# DisplayBank.net
KiCad netlist of a schematic drawn in EAGLE
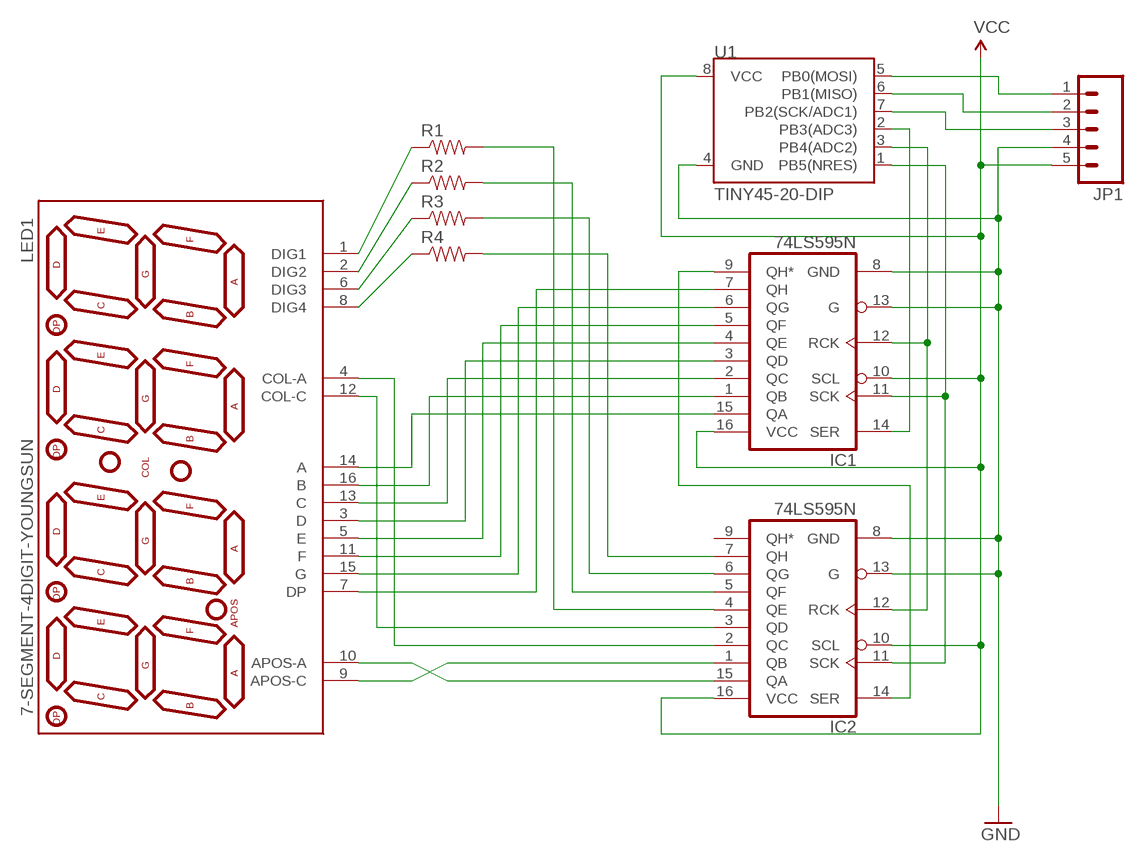
[diagram p0: schematic, sheet 1]

(export (version "E")
  (design (tool "Eeschema 10.0.6"))
  (components
    (comp (ref "IC1")
      (value "74LS595N")
      (footprint "eagle-import:DIL16")
      (libsource (lib "eagle-import") (part "74595NLS"))
    )
    (comp (ref "IC2")
      (value "74LS595N")
      (footprint "eagle-import:DIL16")
      (libsource (lib "eagle-import") (part "74595NLS"))
    )
    (comp (ref "JP1")
      (value "M05NO_SILK")
      (footprint "eagle-import:1X05_NO_SILK")
      (libsource (lib "eagle-import") (part "M05NO_SILK"))
    )
    (comp (ref "LED1")
      (value "7-SEGMENT-4DIGIT-YOUNGSUN")
      (footprint "eagle-import:7-SEGMENT-4DIGIT-YOUNGSUN")
      (libsource (lib "eagle-import") (part "7-SEGMENT-4DIGIT-YOUNGSUN"))
    )
    (comp (ref "R1")
      (value "RESISTORPTH-1/4W")
      (footprint "eagle-import:AXIAL-0.4")
      (libsource (lib "eagle-import") (part "RESISTORPTH-1/4W"))
    )
    (comp (ref "R2")
      (value "RESISTORPTH-1/4W")
      (footprint "eagle-import:AXIAL-0.4")
      (libsource (lib "eagle-import") (part "RESISTORPTH-1/4W"))
    )
    (comp (ref "R3")
      (value "RESISTORPTH-1/4W")
      (footprint "eagle-import:AXIAL-0.4")
      (libsource (lib "eagle-import") (part "RESISTORPTH-1/4W"))
    )
    (comp (ref "R4")
      (value "RESISTORPTH-1/4W")
      (footprint "eagle-import:AXIAL-0.4")
      (libsource (lib "eagle-import") (part "RESISTORPTH-1/4W"))
    )
    (comp (ref "U1")
      (value "TINY45-20-DIP")
      (footprint "eagle-import:DIP08")
      (libsource (lib "eagle-import") (part "ATTINY45TINY45-20-DIP"))
    )
  )
  (nets
    (net (code "1") (name "GND") (class "Default")
      (node (ref "IC1") (pin "13") (pinfunction "G_13") (pintype "input"))
      (node (ref "IC1") (pin "8") (pinfunction "GND_8") (pintype "power_in"))
      (node (ref "IC2") (pin "13") (pinfunction "G_13") (pintype "input"))
      (node (ref "IC2") (pin "8") (pinfunction "GND_8") (pintype "power_in"))
      (node (ref "JP1") (pin "4") (pinfunction "4_4") (pintype "passive"))
      (node (ref "U1") (pin "4") (pinfunction "GND_4") (pintype "bidirectional"))
    )
    (net (code "2") (name "Net-(IC1-QA)") (class "Default")
      (node (ref "IC1") (pin "15") (pinfunction "QA_15") (pintype "tri_state"))
      (node (ref "LED1") (pin "14") (pinfunction "A_14") (pintype "bidirectional"))
    )
    (net (code "3") (name "Net-(IC1-QB)") (class "Default")
      (node (ref "IC1") (pin "1") (pinfunction "QB_1") (pintype "tri_state"))
      (node (ref "LED1") (pin "16") (pinfunction "B_16") (pintype "bidirectional"))
    )
    (net (code "4") (name "Net-(IC1-QC)") (class "Default")
      (node (ref "IC1") (pin "2") (pinfunction "QC_2") (pintype "tri_state"))
      (node (ref "LED1") (pin "13") (pinfunction "C_13") (pintype "bidirectional"))
    )
    (net (code "5") (name "Net-(IC1-QD)") (class "Default")
      (node (ref "IC1") (pin "3") (pinfunction "QD_3") (pintype "tri_state"))
      (node (ref "LED1") (pin "3") (pinfunction "D_3") (pintype "bidirectional"))
    )
    (net (code "6") (name "Net-(IC1-QE)") (class "Default")
      (node (ref "IC1") (pin "4") (pinfunction "QE_4") (pintype "tri_state"))
      (node (ref "LED1") (pin "5") (pinfunction "E_5") (pintype "bidirectional"))
    )
    (net (code "7") (name "Net-(IC1-QF)") (class "Default")
      (node (ref "IC1") (pin "5") (pinfunction "QF_5") (pintype "tri_state"))
      (node (ref "LED1") (pin "11") (pinfunction "F_11") (pintype "bidirectional"))
    )
    (net (code "8") (name "Net-(IC1-QG)") (class "Default")
      (node (ref "IC1") (pin "6") (pinfunction "QG_6") (pintype "tri_state"))
      (node (ref "LED1") (pin "15") (pinfunction "G_15") (pintype "bidirectional"))
    )
    (net (code "9") (name "Net-(IC1-QH)") (class "Default")
      (node (ref "IC1") (pin "7") (pinfunction "QH_7") (pintype "tri_state"))
      (node (ref "LED1") (pin "7") (pinfunction "DP_7") (pintype "bidirectional"))
    )
    (net (code "10") (name "Net-(IC1-QH*)") (class "Default")
      (node (ref "IC1") (pin "9") (pinfunction "QH*_9") (pintype "tri_state"))
      (node (ref "IC2") (pin "14") (pinfunction "SER_14") (pintype "input"))
    )
    (net (code "11") (name "Net-(IC1-RCK)") (class "Default")
      (node (ref "IC1") (pin "12") (pinfunction "RCK_12") (pintype "input"))
      (node (ref "IC2") (pin "12") (pinfunction "RCK_12") (pintype "input"))
      (node (ref "U1") (pin "3") (pinfunction "PB4(ADC2)_3") (pintype "bidirectional"))
    )
    (net (code "12") (name "Net-(IC1-SCK)") (class "Default")
      (node (ref "IC1") (pin "11") (pinfunction "SCK_11") (pintype "input"))
      (node (ref "IC2") (pin "11") (pinfunction "SCK_11") (pintype "input"))
      (node (ref "U1") (pin "1") (pinfunction "PB5(NRES)_1") (pintype "bidirectional"))
    )
    (net (code "13") (name "Net-(IC1-SER)") (class "Default")
      (node (ref "IC1") (pin "14") (pinfunction "SER_14") (pintype "input"))
      (node (ref "U1") (pin "2") (pinfunction "PB3(ADC3)_2") (pintype "bidirectional"))
    )
    (net (code "14") (name "Net-(IC2-QA)") (class "Default")
      (node (ref "IC2") (pin "15") (pinfunction "QA_15") (pintype "tri_state"))
      (node (ref "LED1") (pin "10") (pinfunction "APOS-A_10") (pintype "bidirectional"))
    )
    (net (code "15") (name "Net-(IC2-QB)") (class "Default")
      (node (ref "IC2") (pin "1") (pinfunction "QB_1") (pintype "tri_state"))
      (node (ref "LED1") (pin "9") (pinfunction "APOS-C_9") (pintype "bidirectional"))
    )
    (net (code "16") (name "Net-(IC2-QC)") (class "Default")
      (node (ref "IC2") (pin "2") (pinfunction "QC_2") (pintype "tri_state"))
      (node (ref "LED1") (pin "4") (pinfunction "COL-A_4") (pintype "bidirectional"))
    )
    (net (code "17") (name "Net-(IC2-QD)") (class "Default")
      (node (ref "IC2") (pin "3") (pinfunction "QD_3") (pintype "tri_state"))
      (node (ref "LED1") (pin "12") (pinfunction "COL-C_12") (pintype "bidirectional"))
    )
    (net (code "18") (name "Net-(IC2-QE)") (class "Default")
      (node (ref "IC2") (pin "4") (pinfunction "QE_4") (pintype "tri_state"))
      (node (ref "R1") (pin "P$2") (pinfunction "2_P$2") (pintype "passive"))
    )
    (net (code "19") (name "Net-(IC2-QF)") (class "Default")
      (node (ref "IC2") (pin "5") (pinfunction "QF_5") (pintype "tri_state"))
      (node (ref "R2") (pin "P$2") (pinfunction "2_P$2") (pintype "passive"))
    )
    (net (code "20") (name "Net-(IC2-QG)") (class "Default")
      (node (ref "IC2") (pin "6") (pinfunction "QG_6") (pintype "tri_state"))
      (node (ref "R3") (pin "P$2") (pinfunction "2_P$2") (pintype "passive"))
    )
    (net (code "21") (name "Net-(IC2-QH)") (class "Default")
      (node (ref "IC2") (pin "7") (pinfunction "QH_7") (pintype "tri_state"))
      (node (ref "R4") (pin "P$2") (pinfunction "2_P$2") (pintype "passive"))
    )
    (net (code "22") (name "Net-(LED1-DIG1)") (class "Default")
      (node (ref "LED1") (pin "1") (pinfunction "DIG1_1") (pintype "bidirectional"))
      (node (ref "R1") (pin "P$1") (pinfunction "1_P$1") (pintype "passive"))
    )
    (net (code "23") (name "Net-(LED1-DIG2)") (class "Default")
      (node (ref "LED1") (pin "2") (pinfunction "DIG2_2") (pintype "bidirectional"))
      (node (ref "R2") (pin "P$1") (pinfunction "1_P$1") (pintype "passive"))
    )
    (net (code "24") (name "Net-(LED1-DIG3)") (class "Default")
      (node (ref "LED1") (pin "6") (pinfunction "DIG3_6") (pintype "bidirectional"))
      (node (ref "R3") (pin "P$1") (pinfunction "1_P$1") (pintype "passive"))
    )
    (net (code "25") (name "Net-(LED1-DIG4)") (class "Default")
      (node (ref "LED1") (pin "8") (pinfunction "DIG4_8") (pintype "bidirectional"))
      (node (ref "R4") (pin "P$1") (pinfunction "1_P$1") (pintype "passive"))
    )
    (net (code "26") (name "Net-(U1-PB0(MOSI))") (class "Default")
      (node (ref "JP1") (pin "1") (pinfunction "1_1") (pintype "passive"))
      (node (ref "U1") (pin "5") (pinfunction "PB0(MOSI)_5") (pintype "bidirectional"))
    )
    (net (code "27") (name "Net-(U1-PB1(MISO))") (class "Default")
      (node (ref "JP1") (pin "2") (pinfunction "2_2") (pintype "passive"))
      (node (ref "U1") (pin "6") (pinfunction "PB1(MISO)_6") (pintype "bidirectional"))
    )
    (net (code "28") (name "Net-(U1-PB2(SCK{slash}ADC1))") (class "Default")
      (node (ref "JP1") (pin "3") (pinfunction "3_3") (pintype "passive"))
      (node (ref "U1") (pin "7") (pinfunction "PB2(SCK/ADC1)_7") (pintype "bidirectional"))
    )
    (net (code "29") (name "VCC") (class "Default")
      (node (ref "IC1") (pin "10") (pinfunction "SCL_10") (pintype "input"))
      (node (ref "IC1") (pin "16") (pinfunction "VCC_16") (pintype "power_in"))
      (node (ref "IC2") (pin "10") (pinfunction "SCL_10") (pintype "input"))
      (node (ref "IC2") (pin "16") (pinfunction "VCC_16") (pintype "power_in"))
      (node (ref "JP1") (pin "5") (pinfunction "5_5") (pintype "passive"))
      (node (ref "U1") (pin "8") (pinfunction "VCC_8") (pintype "bidirectional"))
    )
    (net (code "30") (name "unconnected-(IC2-QH*-Pad9)") (class "Default")
      (node (ref "IC2") (pin "9") (pinfunction "QH*_9") (pintype "tri_state"))
    )
  )
)
